# UltrasonicSensorArray.net
KiCad netlist of a schematic drawn in EAGLE
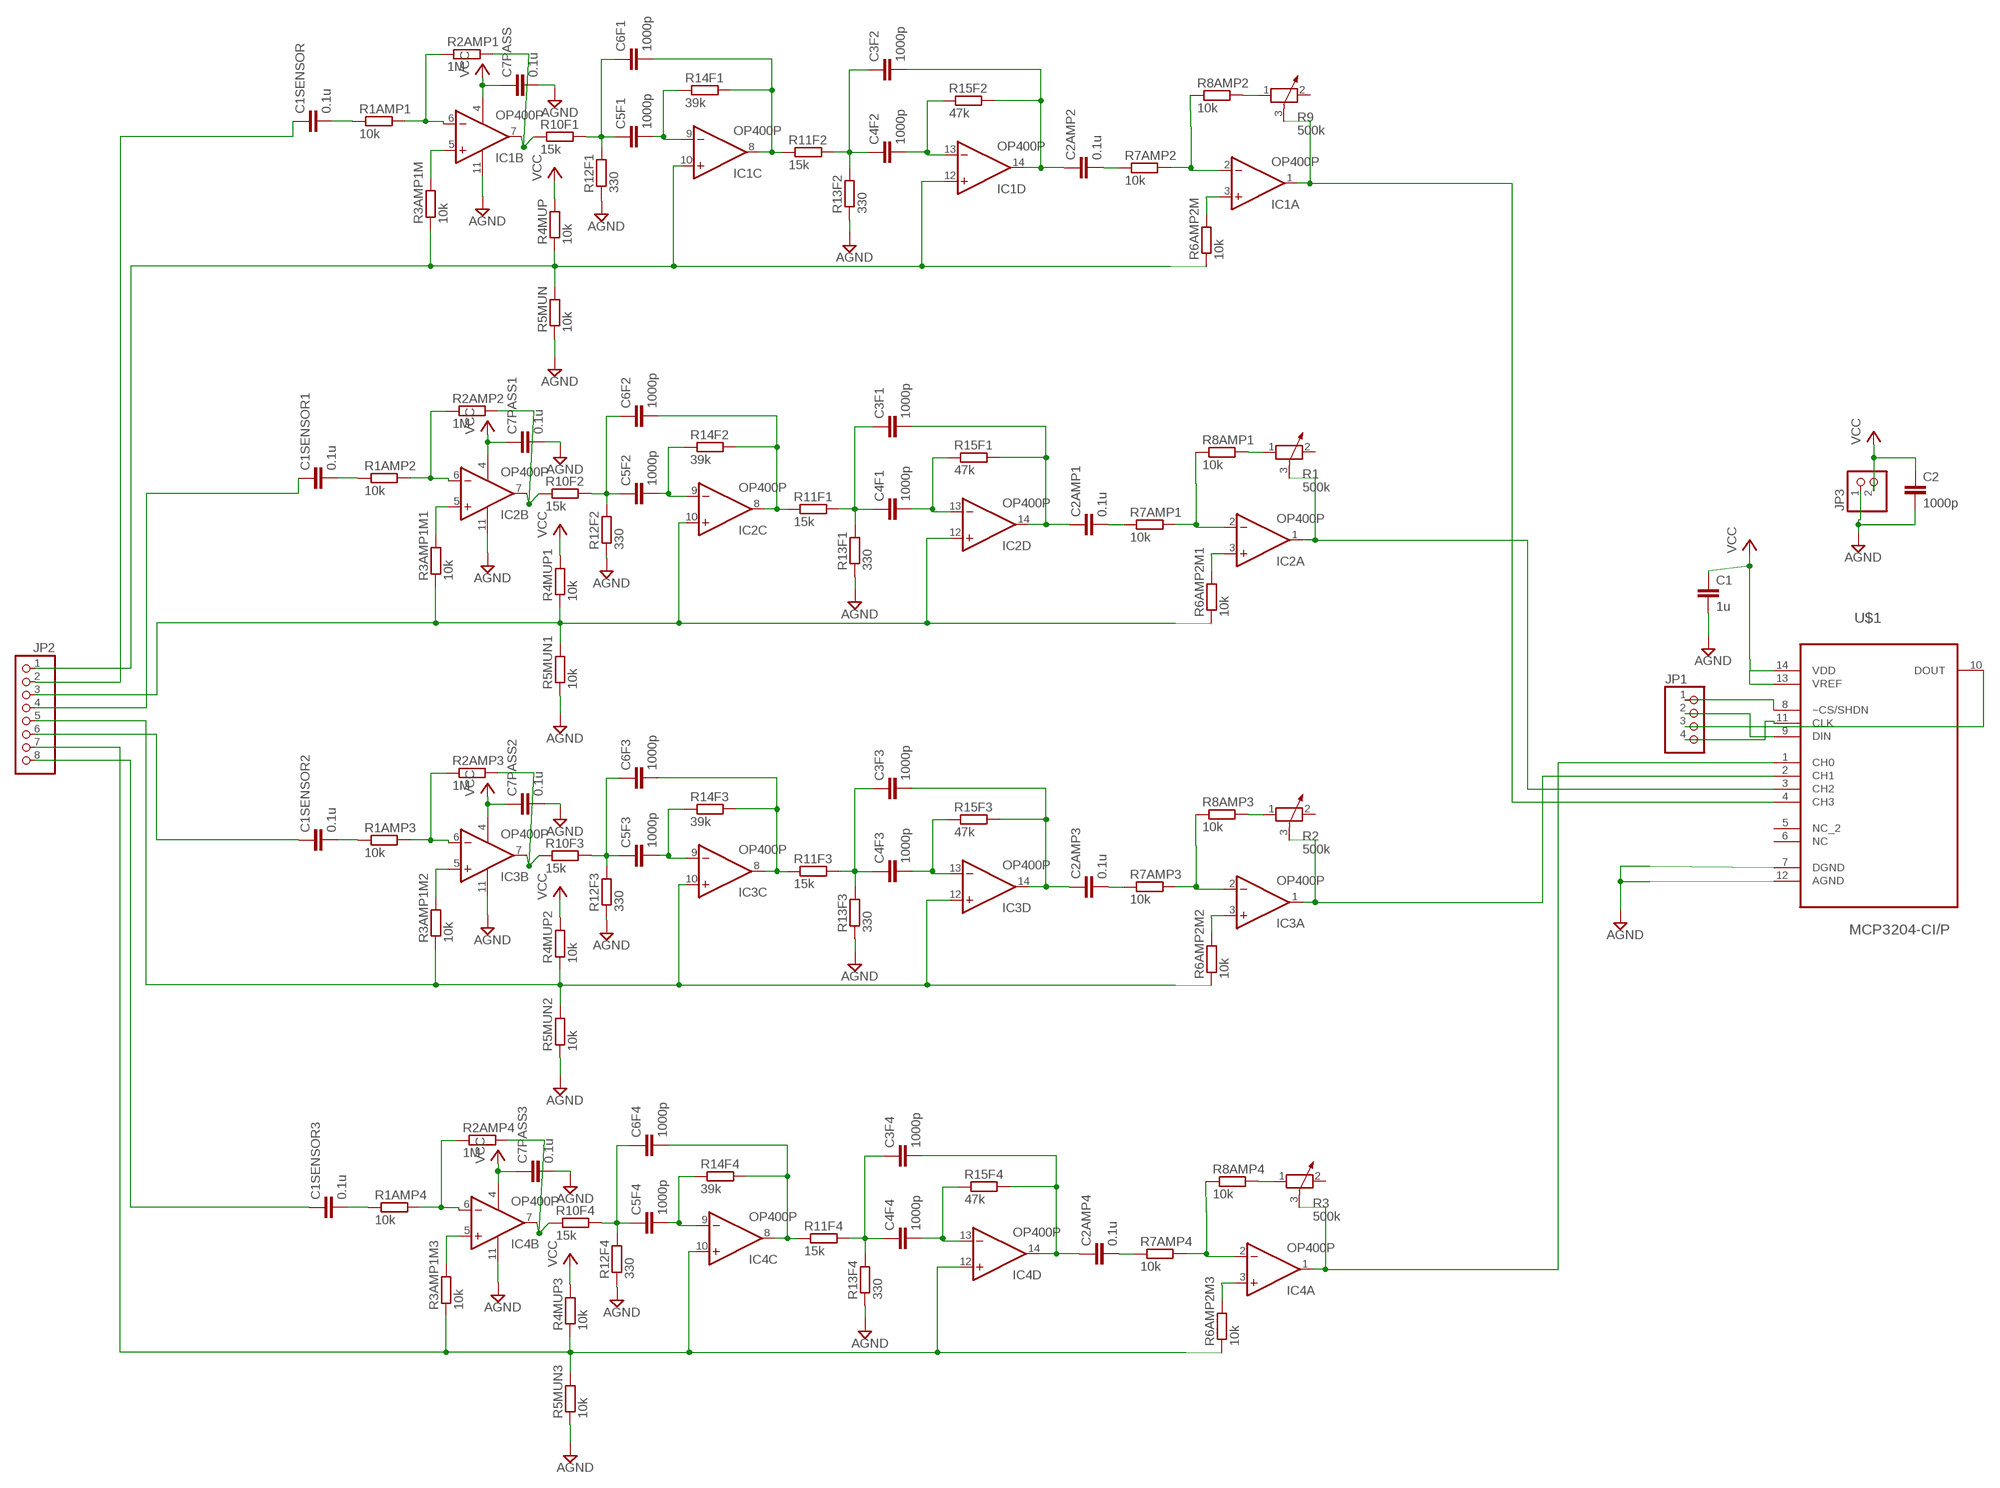
[diagram p0: schematic, sheet 1]

(export (version "E")
  (design (tool "Eeschema 10.0.6"))
  (components
    (comp (ref "C1")
      (value "1u")
      (footprint "eagle-import:C0603K")
      (libsource (lib "eagle-import") (part "C-EUC0603K"))
    )
    (comp (ref "C1SENSOR")
      (value "0.1u")
      (footprint "eagle-import:C0603K")
      (libsource (lib "eagle-import") (part "C-EUC0603K"))
    )
    (comp (ref "C1SENSOR1")
      (value "0.1u")
      (footprint "eagle-import:C0603K")
      (libsource (lib "eagle-import") (part "C-EUC0603K"))
    )
    (comp (ref "C1SENSOR2")
      (value "0.1u")
      (footprint "eagle-import:C0603K")
      (libsource (lib "eagle-import") (part "C-EUC0603K"))
    )
    (comp (ref "C1SENSOR3")
      (value "0.1u")
      (footprint "eagle-import:C0603K")
      (libsource (lib "eagle-import") (part "C-EUC0603K"))
    )
    (comp (ref "C2")
      (value "1000p")
      (footprint "eagle-import:C0603K")
      (libsource (lib "eagle-import") (part "C-EUC0603K"))
    )
    (comp (ref "C2AMP1")
      (value "0.1u")
      (footprint "eagle-import:C0603K")
      (libsource (lib "eagle-import") (part "C-EUC0603K"))
    )
    (comp (ref "C2AMP2")
      (value "0.1u")
      (footprint "eagle-import:C0603K")
      (libsource (lib "eagle-import") (part "C-EUC0603K"))
    )
    (comp (ref "C2AMP3")
      (value "0.1u")
      (footprint "eagle-import:C0603K")
      (libsource (lib "eagle-import") (part "C-EUC0603K"))
    )
    (comp (ref "C2AMP4")
      (value "0.1u")
      (footprint "eagle-import:C0603K")
      (libsource (lib "eagle-import") (part "C-EUC0603K"))
    )
    (comp (ref "C3F1")
      (value "1000p")
      (footprint "eagle-import:C0603K")
      (libsource (lib "eagle-import") (part "C-EUC0603K"))
    )
    (comp (ref "C3F2")
      (value "1000p")
      (footprint "eagle-import:C0603K")
      (libsource (lib "eagle-import") (part "C-EUC0603K"))
    )
    (comp (ref "C3F3")
      (value "1000p")
      (footprint "eagle-import:C0603K")
      (libsource (lib "eagle-import") (part "C-EUC0603K"))
    )
    (comp (ref "C3F4")
      (value "1000p")
      (footprint "eagle-import:C0603K")
      (libsource (lib "eagle-import") (part "C-EUC0603K"))
    )
    (comp (ref "C4F1")
      (value "1000p")
      (footprint "eagle-import:C0603K")
      (libsource (lib "eagle-import") (part "C-EUC0603K"))
    )
    (comp (ref "C4F2")
      (value "1000p")
      (footprint "eagle-import:C0603K")
      (libsource (lib "eagle-import") (part "C-EUC0603K"))
    )
    (comp (ref "C4F3")
      (value "1000p")
      (footprint "eagle-import:C0603K")
      (libsource (lib "eagle-import") (part "C-EUC0603K"))
    )
    (comp (ref "C4F4")
      (value "1000p")
      (footprint "eagle-import:C0603K")
      (libsource (lib "eagle-import") (part "C-EUC0603K"))
    )
    (comp (ref "C5F1")
      (value "1000p")
      (footprint "eagle-import:C0603K")
      (libsource (lib "eagle-import") (part "C-EUC0603K"))
    )
    (comp (ref "C5F2")
      (value "1000p")
      (footprint "eagle-import:C0603K")
      (libsource (lib "eagle-import") (part "C-EUC0603K"))
    )
    (comp (ref "C5F3")
      (value "1000p")
      (footprint "eagle-import:C0603K")
      (libsource (lib "eagle-import") (part "C-EUC0603K"))
    )
    (comp (ref "C5F4")
      (value "1000p")
      (footprint "eagle-import:C0603K")
      (libsource (lib "eagle-import") (part "C-EUC0603K"))
    )
    (comp (ref "C6F1")
      (value "1000p")
      (footprint "eagle-import:C0603K")
      (libsource (lib "eagle-import") (part "C-EUC0603K"))
    )
    (comp (ref "C6F2")
      (value "1000p")
      (footprint "eagle-import:C0603K")
      (libsource (lib "eagle-import") (part "C-EUC0603K"))
    )
    (comp (ref "C6F3")
      (value "1000p")
      (footprint "eagle-import:C0603K")
      (libsource (lib "eagle-import") (part "C-EUC0603K"))
    )
    (comp (ref "C6F4")
      (value "1000p")
      (footprint "eagle-import:C0603K")
      (libsource (lib "eagle-import") (part "C-EUC0603K"))
    )
    (comp (ref "C7PASS")
      (value "0.1u")
      (footprint "eagle-import:C0603K")
      (libsource (lib "eagle-import") (part "C-EUC0603K"))
    )
    (comp (ref "C7PASS1")
      (value "0.1u")
      (footprint "eagle-import:C0603K")
      (libsource (lib "eagle-import") (part "C-EUC0603K"))
    )
    (comp (ref "C7PASS2")
      (value "0.1u")
      (footprint "eagle-import:C0603K")
      (libsource (lib "eagle-import") (part "C-EUC0603K"))
    )
    (comp (ref "C7PASS3")
      (value "0.1u")
      (footprint "eagle-import:C0603K")
      (libsource (lib "eagle-import") (part "C-EUC0603K"))
    )
    (comp (ref "IC1")
      (value "OP400P")
      (footprint "eagle-import:DIL14")
      (libsource (lib "eagle-import") (part "OP400P"))
    )
    (comp (ref "IC2")
      (value "OP400P")
      (footprint "eagle-import:DIL14")
      (libsource (lib "eagle-import") (part "OP400P"))
    )
    (comp (ref "IC3")
      (value "OP400P")
      (footprint "eagle-import:DIL14")
      (libsource (lib "eagle-import") (part "OP400P"))
    )
    (comp (ref "IC4")
      (value "OP400P")
      (footprint "eagle-import:DIL14")
      (libsource (lib "eagle-import") (part "OP400P"))
    )
    (comp (ref "JP1")
      (value "PINHD-1X4")
      (footprint "eagle-import:1X04")
      (libsource (lib "eagle-import") (part "PINHD-1X4"))
    )
    (comp (ref "JP2")
      (value "PINHD-1X8")
      (footprint "eagle-import:1X08")
      (libsource (lib "eagle-import") (part "PINHD-1X8"))
    )
    (comp (ref "JP3")
      (value "PINHD-1X2")
      (footprint "eagle-import:1X02")
      (libsource (lib "eagle-import") (part "PINHD-1X2"))
    )
    (comp (ref "R1")
      (value "500k")
      (footprint "eagle-import:PT-10")
      (libsource (lib "eagle-import") (part "POTENTIOMETER_PT-10"))
    )
    (comp (ref "R1AMP1")
      (value "10k")
      (footprint "eagle-import:R0603")
      (libsource (lib "eagle-import") (part "R-EU_R0603"))
    )
    (comp (ref "R1AMP2")
      (value "10k")
      (footprint "eagle-import:R0603")
      (libsource (lib "eagle-import") (part "R-EU_R0603"))
    )
    (comp (ref "R1AMP3")
      (value "10k")
      (footprint "eagle-import:R0603")
      (libsource (lib "eagle-import") (part "R-EU_R0603"))
    )
    (comp (ref "R1AMP4")
      (value "10k")
      (footprint "eagle-import:R0603")
      (libsource (lib "eagle-import") (part "R-EU_R0603"))
    )
    (comp (ref "R2")
      (value "500k")
      (footprint "eagle-import:PT-10")
      (libsource (lib "eagle-import") (part "POTENTIOMETER_PT-10"))
    )
    (comp (ref "R2AMP1")
      (value "1M")
      (footprint "eagle-import:R0603")
      (libsource (lib "eagle-import") (part "R-EU_R0603"))
    )
    (comp (ref "R2AMP2")
      (value "1M")
      (footprint "eagle-import:R0603")
      (libsource (lib "eagle-import") (part "R-EU_R0603"))
    )
    (comp (ref "R2AMP3")
      (value "1M")
      (footprint "eagle-import:R0603")
      (libsource (lib "eagle-import") (part "R-EU_R0603"))
    )
    (comp (ref "R2AMP4")
      (value "1M")
      (footprint "eagle-import:R0603")
      (libsource (lib "eagle-import") (part "R-EU_R0603"))
    )
    (comp (ref "R3")
      (value "500k")
      (footprint "eagle-import:PT-10")
      (libsource (lib "eagle-import") (part "POTENTIOMETER_PT-10"))
    )
    (comp (ref "R3AMP1M")
      (value "10k")
      (footprint "eagle-import:R0603")
      (libsource (lib "eagle-import") (part "R-EU_R0603"))
    )
    (comp (ref "R3AMP1M1")
      (value "10k")
      (footprint "eagle-import:R0603")
      (libsource (lib "eagle-import") (part "R-EU_R0603"))
    )
    (comp (ref "R3AMP1M2")
      (value "10k")
      (footprint "eagle-import:R0603")
      (libsource (lib "eagle-import") (part "R-EU_R0603"))
    )
    (comp (ref "R3AMP1M3")
      (value "10k")
      (footprint "eagle-import:R0603")
      (libsource (lib "eagle-import") (part "R-EU_R0603"))
    )
    (comp (ref "R4MUP")
      (value "10k")
      (footprint "eagle-import:R0603")
      (libsource (lib "eagle-import") (part "R-EU_R0603"))
    )
    (comp (ref "R4MUP1")
      (value "10k")
      (footprint "eagle-import:R0603")
      (libsource (lib "eagle-import") (part "R-EU_R0603"))
    )
    (comp (ref "R4MUP2")
      (value "10k")
      (footprint "eagle-import:R0603")
      (libsource (lib "eagle-import") (part "R-EU_R0603"))
    )
    (comp (ref "R4MUP3")
      (value "10k")
      (footprint "eagle-import:R0603")
      (libsource (lib "eagle-import") (part "R-EU_R0603"))
    )
    (comp (ref "R5MUN")
      (value "10k")
      (footprint "eagle-import:R0603")
      (libsource (lib "eagle-import") (part "R-EU_R0603"))
    )
    (comp (ref "R5MUN1")
      (value "10k")
      (footprint "eagle-import:R0603")
      (libsource (lib "eagle-import") (part "R-EU_R0603"))
    )
    (comp (ref "R5MUN2")
      (value "10k")
      (footprint "eagle-import:R0603")
      (libsource (lib "eagle-import") (part "R-EU_R0603"))
    )
    (comp (ref "R5MUN3")
      (value "10k")
      (footprint "eagle-import:R0603")
      (libsource (lib "eagle-import") (part "R-EU_R0603"))
    )
    (comp (ref "R6AMP2M")
      (value "10k")
      (footprint "eagle-import:R0603")
      (libsource (lib "eagle-import") (part "R-EU_R0603"))
    )
    (comp (ref "R6AMP2M1")
      (value "10k")
      (footprint "eagle-import:R0603")
      (libsource (lib "eagle-import") (part "R-EU_R0603"))
    )
    (comp (ref "R6AMP2M2")
      (value "10k")
      (footprint "eagle-import:R0603")
      (libsource (lib "eagle-import") (part "R-EU_R0603"))
    )
    (comp (ref "R6AMP2M3")
      (value "10k")
      (footprint "eagle-import:R0603")
      (libsource (lib "eagle-import") (part "R-EU_R0603"))
    )
    (comp (ref "R7AMP1")
      (value "10k")
      (footprint "eagle-import:R0603")
      (libsource (lib "eagle-import") (part "R-EU_R0603"))
    )
    (comp (ref "R7AMP2")
      (value "10k")
      (footprint "eagle-import:R0603")
      (libsource (lib "eagle-import") (part "R-EU_R0603"))
    )
    (comp (ref "R7AMP3")
      (value "10k")
      (footprint "eagle-import:R0603")
      (libsource (lib "eagle-import") (part "R-EU_R0603"))
    )
    (comp (ref "R7AMP4")
      (value "10k")
      (footprint "eagle-import:R0603")
      (libsource (lib "eagle-import") (part "R-EU_R0603"))
    )
    (comp (ref "R8AMP1")
      (value "10k")
      (footprint "eagle-import:R0603")
      (libsource (lib "eagle-import") (part "R-EU_R0603"))
    )
    (comp (ref "R8AMP2")
      (value "10k")
      (footprint "eagle-import:R0603")
      (libsource (lib "eagle-import") (part "R-EU_R0603"))
    )
    (comp (ref "R8AMP3")
      (value "10k")
      (footprint "eagle-import:R0603")
      (libsource (lib "eagle-import") (part "R-EU_R0603"))
    )
    (comp (ref "R8AMP4")
      (value "10k")
      (footprint "eagle-import:R0603")
      (libsource (lib "eagle-import") (part "R-EU_R0603"))
    )
    (comp (ref "R9")
      (value "500k")
      (footprint "eagle-import:PT-10")
      (libsource (lib "eagle-import") (part "POTENTIOMETER_PT-10"))
    )
    (comp (ref "R10F1")
      (value "15k")
      (footprint "eagle-import:R0603")
      (libsource (lib "eagle-import") (part "R-EU_R0603"))
    )
    (comp (ref "R10F2")
      (value "15k")
      (footprint "eagle-import:R0603")
      (libsource (lib "eagle-import") (part "R-EU_R0603"))
    )
    (comp (ref "R10F3")
      (value "15k")
      (footprint "eagle-import:R0603")
      (libsource (lib "eagle-import") (part "R-EU_R0603"))
    )
    (comp (ref "R10F4")
      (value "15k")
      (footprint "eagle-import:R0603")
      (libsource (lib "eagle-import") (part "R-EU_R0603"))
    )
    (comp (ref "R11F1")
      (value "15k")
      (footprint "eagle-import:R0603")
      (libsource (lib "eagle-import") (part "R-EU_R0603"))
    )
    (comp (ref "R11F2")
      (value "15k")
      (footprint "eagle-import:R0603")
      (libsource (lib "eagle-import") (part "R-EU_R0603"))
    )
    (comp (ref "R11F3")
      (value "15k")
      (footprint "eagle-import:R0603")
      (libsource (lib "eagle-import") (part "R-EU_R0603"))
    )
    (comp (ref "R11F4")
      (value "15k")
      (footprint "eagle-import:R0603")
      (libsource (lib "eagle-import") (part "R-EU_R0603"))
    )
    (comp (ref "R12F1")
      (value "330")
      (footprint "eagle-import:R0603")
      (libsource (lib "eagle-import") (part "R-EU_R0603"))
    )
    (comp (ref "R12F2")
      (value "330")
      (footprint "eagle-import:R0603")
      (libsource (lib "eagle-import") (part "R-EU_R0603"))
    )
    (comp (ref "R12F3")
      (value "330")
      (footprint "eagle-import:R0603")
      (libsource (lib "eagle-import") (part "R-EU_R0603"))
    )
    (comp (ref "R12F4")
      (value "330")
      (footprint "eagle-import:R0603")
      (libsource (lib "eagle-import") (part "R-EU_R0603"))
    )
    (comp (ref "R13F1")
      (value "330")
      (footprint "eagle-import:R0603")
      (libsource (lib "eagle-import") (part "R-EU_R0603"))
    )
    (comp (ref "R13F2")
      (value "330")
      (footprint "eagle-import:R0603")
      (libsource (lib "eagle-import") (part "R-EU_R0603"))
    )
    (comp (ref "R13F3")
      (value "330")
      (footprint "eagle-import:R0603")
      (libsource (lib "eagle-import") (part "R-EU_R0603"))
    )
    (comp (ref "R13F4")
      (value "330")
      (footprint "eagle-import:R0603")
      (libsource (lib "eagle-import") (part "R-EU_R0603"))
    )
    (comp (ref "R14F1")
      (value "39k")
      (footprint "eagle-import:0207_7")
      (libsource (lib "eagle-import") (part "R-EU_0207/7"))
    )
    (comp (ref "R14F2")
      (value "39k")
      (footprint "eagle-import:0207_7")
      (libsource (lib "eagle-import") (part "R-EU_0207/7"))
    )
    (comp (ref "R14F3")
      (value "39k")
      (footprint "eagle-import:0207_7")
      (libsource (lib "eagle-import") (part "R-EU_0207/7"))
    )
    (comp (ref "R14F4")
      (value "39k")
      (footprint "eagle-import:0207_7")
      (libsource (lib "eagle-import") (part "R-EU_0207/7"))
    )
    (comp (ref "R15F1")
      (value "47k")
      (footprint "eagle-import:0207_7")
      (libsource (lib "eagle-import") (part "R-EU_0207/7"))
    )
    (comp (ref "R15F2")
      (value "47k")
      (footprint "eagle-import:0207_7")
      (libsource (lib "eagle-import") (part "R-EU_0207/7"))
    )
    (comp (ref "R15F3")
      (value "47k")
      (footprint "eagle-import:0207_7")
      (libsource (lib "eagle-import") (part "R-EU_0207/7"))
    )
    (comp (ref "R15F4")
      (value "47k")
      (footprint "eagle-import:0207_7")
      (libsource (lib "eagle-import") (part "R-EU_0207/7"))
    )
    (comp (ref "U$1")
      (value "MCP3204-CI/P")
      (footprint "eagle-import:DIP254P762X432-14")
      (fields (field (name "MF") "Microchip"))
      (libsource (lib "eagle-import") (part "MCP3204-CI/P"))
    )
  )
  (nets
    (net (code "1") (name "AGND") (class "Default")
      (node (ref "C1") (pin "2") (pinfunction "2_2") (pintype "passive"))
      (node (ref "C2") (pin "2") (pinfunction "2_2") (pintype "passive"))
      (node (ref "C7PASS") (pin "2") (pinfunction "2_2") (pintype "passive"))
      (node (ref "C7PASS1") (pin "2") (pinfunction "2_2") (pintype "passive"))
      (node (ref "C7PASS2") (pin "2") (pinfunction "2_2") (pintype "passive"))
      (node (ref "C7PASS3") (pin "2") (pinfunction "2_2") (pintype "passive"))
      (node (ref "IC1") (pin "11") (pinfunction "V-_11") (pintype "power_in"))
      (node (ref "IC2") (pin "11") (pinfunction "V-_11") (pintype "power_in"))
      (node (ref "IC3") (pin "11") (pinfunction "V-_11") (pintype "power_in"))
      (node (ref "IC4") (pin "11") (pinfunction "V-_11") (pintype "power_in"))
      (node (ref "JP3") (pin "1") (pinfunction "1_1") (pintype "passive"))
      (node (ref "R12F1") (pin "1") (pinfunction "1_1") (pintype "passive"))
      (node (ref "R12F2") (pin "1") (pinfunction "1_1") (pintype "passive"))
      (node (ref "R12F3") (pin "1") (pinfunction "1_1") (pintype "passive"))
      (node (ref "R12F4") (pin "1") (pinfunction "1_1") (pintype "passive"))
      (node (ref "R13F1") (pin "1") (pinfunction "1_1") (pintype "passive"))
      (node (ref "R13F2") (pin "1") (pinfunction "1_1") (pintype "passive"))
      (node (ref "R13F3") (pin "1") (pinfunction "1_1") (pintype "passive"))
      (node (ref "R13F4") (pin "1") (pinfunction "1_1") (pintype "passive"))
      (node (ref "R5MUN") (pin "1") (pinfunction "1_1") (pintype "passive"))
      (node (ref "R5MUN1") (pin "1") (pinfunction "1_1") (pintype "passive"))
      (node (ref "R5MUN2") (pin "1") (pinfunction "1_1") (pintype "passive"))
      (node (ref "R5MUN3") (pin "1") (pinfunction "1_1") (pintype "passive"))
      (node (ref "U$1") (pin "12") (pinfunction "AGND_12") (pintype "passive"))
      (node (ref "U$1") (pin "7") (pinfunction "DGND_7") (pintype "passive"))
    )
    (net (code "2") (name "Net-(C1SENSOR-Pad1)") (class "Default")
      (node (ref "C1SENSOR") (pin "1") (pinfunction "1_1") (pintype "passive"))
      (node (ref "JP2") (pin "2") (pinfunction "2_2") (pintype "passive"))
    )
    (net (code "3") (name "Net-(C1SENSOR-Pad2)") (class "Default")
      (node (ref "C1SENSOR") (pin "2") (pinfunction "2_2") (pintype "passive"))
      (node (ref "R1AMP1") (pin "1") (pinfunction "1_1") (pintype "passive"))
    )
    (net (code "4") (name "Net-(C1SENSOR1-Pad1)") (class "Default")
      (node (ref "C1SENSOR1") (pin "1") (pinfunction "1_1") (pintype "passive"))
      (node (ref "JP2") (pin "4") (pinfunction "4_4") (pintype "passive"))
    )
    (net (code "5") (name "Net-(C1SENSOR1-Pad2)") (class "Default")
      (node (ref "C1SENSOR1") (pin "2") (pinfunction "2_2") (pintype "passive"))
      (node (ref "R1AMP2") (pin "1") (pinfunction "1_1") (pintype "passive"))
    )
    (net (code "6") (name "Net-(C1SENSOR2-Pad1)") (class "Default")
      (node (ref "C1SENSOR2") (pin "1") (pinfunction "1_1") (pintype "passive"))
      (node (ref "JP2") (pin "6") (pinfunction "6_6") (pintype "passive"))
    )
    (net (code "7") (name "Net-(C1SENSOR2-Pad2)") (class "Default")
      (node (ref "C1SENSOR2") (pin "2") (pinfunction "2_2") (pintype "passive"))
      (node (ref "R1AMP3") (pin "1") (pinfunction "1_1") (pintype "passive"))
    )
    (net (code "8") (name "Net-(C1SENSOR3-Pad1)") (class "Default")
      (node (ref "C1SENSOR3") (pin "1") (pinfunction "1_1") (pintype "passive"))
      (node (ref "JP2") (pin "8") (pinfunction "8_8") (pintype "passive"))
    )
    (net (code "9") (name "Net-(C1SENSOR3-Pad2)") (class "Default")
      (node (ref "C1SENSOR3") (pin "2") (pinfunction "2_2") (pintype "passive"))
      (node (ref "R1AMP4") (pin "1") (pinfunction "1_1") (pintype "passive"))
    )
    (net (code "10") (name "Net-(C2AMP1-Pad2)") (class "Default")
      (node (ref "C2AMP1") (pin "2") (pinfunction "2_2") (pintype "passive"))
      (node (ref "R7AMP1") (pin "1") (pinfunction "1_1") (pintype "passive"))
    )
    (net (code "11") (name "Net-(C2AMP2-Pad2)") (class "Default")
      (node (ref "C2AMP2") (pin "2") (pinfunction "2_2") (pintype "passive"))
      (node (ref "R7AMP2") (pin "1") (pinfunction "1_1") (pintype "passive"))
    )
    (net (code "12") (name "Net-(C2AMP3-Pad2)") (class "Default")
      (node (ref "C2AMP3") (pin "2") (pinfunction "2_2") (pintype "passive"))
      (node (ref "R7AMP3") (pin "1") (pinfunction "1_1") (pintype "passive"))
    )
    (net (code "13") (name "Net-(C2AMP4-Pad2)") (class "Default")
      (node (ref "C2AMP4") (pin "2") (pinfunction "2_2") (pintype "passive"))
      (node (ref "R7AMP4") (pin "1") (pinfunction "1_1") (pintype "passive"))
    )
    (net (code "14") (name "Net-(C3F1-Pad1)") (class "Default")
      (node (ref "C3F1") (pin "1") (pinfunction "1_1") (pintype "passive"))
      (node (ref "C4F1") (pin "1") (pinfunction "1_1") (pintype "passive"))
      (node (ref "R11F1") (pin "2") (pinfunction "2_2") (pintype "passive"))
      (node (ref "R13F1") (pin "2") (pinfunction "2_2") (pintype "passive"))
    )
    (net (code "15") (name "Net-(C3F2-Pad1)") (class "Default")
      (node (ref "C3F2") (pin "1") (pinfunction "1_1") (pintype "passive"))
      (node (ref "C4F2") (pin "1") (pinfunction "1_1") (pintype "passive"))
      (node (ref "R11F2") (pin "2") (pinfunction "2_2") (pintype "passive"))
      (node (ref "R13F2") (pin "2") (pinfunction "2_2") (pintype "passive"))
    )
    (net (code "16") (name "Net-(C3F3-Pad1)") (class "Default")
      (node (ref "C3F3") (pin "1") (pinfunction "1_1") (pintype "passive"))
      (node (ref "C4F3") (pin "1") (pinfunction "1_1") (pintype "passive"))
      (node (ref "R11F3") (pin "2") (pinfunction "2_2") (pintype "passive"))
      (node (ref "R13F3") (pin "2") (pinfunction "2_2") (pintype "passive"))
    )
    (net (code "17") (name "Net-(C3F4-Pad1)") (class "Default")
      (node (ref "C3F4") (pin "1") (pinfunction "1_1") (pintype "passive"))
      (node (ref "C4F4") (pin "1") (pinfunction "1_1") (pintype "passive"))
      (node (ref "R11F4") (pin "2") (pinfunction "2_2") (pintype "passive"))
      (node (ref "R13F4") (pin "2") (pinfunction "2_2") (pintype "passive"))
    )
    (net (code "18") (name "Net-(C5F1-Pad1)") (class "Default")
      (node (ref "C5F1") (pin "1") (pinfunction "1_1") (pintype "passive"))
      (node (ref "C6F1") (pin "1") (pinfunction "1_1") (pintype "passive"))
      (node (ref "R10F1") (pin "2") (pinfunction "2_2") (pintype "passive"))
      (node (ref "R12F1") (pin "2") (pinfunction "2_2") (pintype "passive"))
    )
    (net (code "19") (name "Net-(C5F2-Pad1)") (class "Default")
      (node (ref "C5F2") (pin "1") (pinfunction "1_1") (pintype "passive"))
      (node (ref "C6F2") (pin "1") (pinfunction "1_1") (pintype "passive"))
      (node (ref "R10F2") (pin "2") (pinfunction "2_2") (pintype "passive"))
      (node (ref "R12F2") (pin "2") (pinfunction "2_2") (pintype "passive"))
    )
    (net (code "20") (name "Net-(C5F3-Pad1)") (class "Default")
      (node (ref "C5F3") (pin "1") (pinfunction "1_1") (pintype "passive"))
      (node (ref "C6F3") (pin "1") (pinfunction "1_1") (pintype "passive"))
      (node (ref "R10F3") (pin "2") (pinfunction "2_2") (pintype "passive"))
      (node (ref "R12F3") (pin "2") (pinfunction "2_2") (pintype "passive"))
    )
    (net (code "21") (name "Net-(C5F4-Pad1)") (class "Default")
      (node (ref "C5F4") (pin "1") (pinfunction "1_1") (pintype "passive"))
      (node (ref "C6F4") (pin "1") (pinfunction "1_1") (pintype "passive"))
      (node (ref "R10F4") (pin "2") (pinfunction "2_2") (pintype "passive"))
      (node (ref "R12F4") (pin "2") (pinfunction "2_2") (pintype "passive"))
    )
    (net (code "22") (name "Net-(IC1A-+IN)") (class "Default")
      (node (ref "IC1") (pin "3") (pinfunction "+IN_3") (pintype "input"))
      (node (ref "R6AMP2M") (pin "2") (pinfunction "2_2") (pintype "passive"))
    )
    (net (code "23") (name "Net-(IC1A--IN)") (class "Default")
      (node (ref "IC1") (pin "2") (pinfunction "-IN_2") (pintype "input"))
      (node (ref "R7AMP2") (pin "2") (pinfunction "2_2") (pintype "passive"))
      (node (ref "R8AMP2") (pin "1") (pinfunction "1_1") (pintype "passive"))
    )
    (net (code "24") (name "Net-(IC1A-OUT)") (class "Default")
      (node (ref "IC1") (pin "1") (pinfunction "OUT_1") (pintype "output"))
      (node (ref "R9") (pin "3") (pinfunction "3_3") (pintype "passive"))
      (node (ref "U$1") (pin "4") (pinfunction "CH3_4") (pintype "input"))
    )
    (net (code "25") (name "Net-(IC1B-+IN)") (class "Default")
      (node (ref "IC1") (pin "5") (pinfunction "+IN_5") (pintype "input"))
      (node (ref "R3AMP1M") (pin "2") (pinfunction "2_2") (pintype "passive"))
    )
    (net (code "26") (name "Net-(IC1B--IN)") (class "Default")
      (node (ref "IC1") (pin "6") (pinfunction "-IN_6") (pintype "input"))
      (node (ref "R1AMP1") (pin "2") (pinfunction "2_2") (pintype "passive"))
      (node (ref "R2AMP1") (pin "1") (pinfunction "1_1") (pintype "passive"))
    )
    (net (code "27") (name "Net-(IC1B-OUT)") (class "Default")
      (node (ref "IC1") (pin "7") (pinfunction "OUT_7") (pintype "output"))
      (node (ref "R10F1") (pin "1") (pinfunction "1_1") (pintype "passive"))
      (node (ref "R2AMP1") (pin "2") (pinfunction "2_2") (pintype "passive"))
    )
    (net (code "28") (name "Net-(IC1C-+IN)") (class "Default")
      (node (ref "IC1") (pin "10") (pinfunction "+IN_10") (pintype "input"))
      (node (ref "IC1") (pin "12") (pinfunction "+IN_12") (pintype "input"))
      (node (ref "JP2") (pin "1") (pinfunction "1_1") (pintype "passive"))
      (node (ref "R3AMP1M") (pin "1") (pinfunction "1_1") (pintype "passive"))
      (node (ref "R4MUP") (pin "1") (pinfunction "1_1") (pintype "passive"))
      (node (ref "R5MUN") (pin "2") (pinfunction "2_2") (pintype "passive"))
      (node (ref "R6AMP2M") (pin "1") (pinfunction "1_1") (pintype "passive"))
    )
    (net (code "29") (name "Net-(IC1C--IN)") (class "Default")
      (node (ref "C5F1") (pin "2") (pinfunction "2_2") (pintype "passive"))
      (node (ref "IC1") (pin "9") (pinfunction "-IN_9") (pintype "input"))
      (node (ref "R14F1") (pin "1") (pinfunction "1_1") (pintype "passive"))
    )
    (net (code "30") (name "Net-(IC1C-OUT)") (class "Default")
      (node (ref "C6F1") (pin "2") (pinfunction "2_2") (pintype "passive"))
      (node (ref "IC1") (pin "8") (pinfunction "OUT_8") (pintype "output"))
      (node (ref "R11F2") (pin "1") (pinfunction "1_1") (pintype "passive"))
      (node (ref "R14F1") (pin "2") (pinfunction "2_2") (pintype "passive"))
    )
    (net (code "31") (name "Net-(IC1D--IN)") (class "Default")
      (node (ref "C4F2") (pin "2") (pinfunction "2_2") (pintype "passive"))
      (node (ref "IC1") (pin "13") (pinfunction "-IN_13") (pintype "input"))
      (node (ref "R15F2") (pin "1") (pinfunction "1_1") (pintype "passive"))
    )
    (net (code "32") (name "Net-(IC1D-OUT)") (class "Default")
      (node (ref "C2AMP2") (pin "1") (pinfunction "1_1") (pintype "passive"))
      (node (ref "C3F2") (pin "2") (pinfunction "2_2") (pintype "passive"))
      (node (ref "IC1") (pin "14") (pinfunction "OUT_14") (pintype "output"))
      (node (ref "R15F2") (pin "2") (pinfunction "2_2") (pintype "passive"))
    )
    (net (code "33") (name "Net-(IC2A-+IN)") (class "Default")
      (node (ref "IC2") (pin "3") (pinfunction "+IN_3") (pintype "input"))
      (node (ref "R6AMP2M1") (pin "2") (pinfunction "2_2") (pintype "passive"))
    )
    (net (code "34") (name "Net-(IC2A--IN)") (class "Default")
      (node (ref "IC2") (pin "2") (pinfunction "-IN_2") (pintype "input"))
      (node (ref "R7AMP1") (pin "2") (pinfunction "2_2") (pintype "passive"))
      (node (ref "R8AMP1") (pin "1") (pinfunction "1_1") (pintype "passive"))
    )
    (net (code "35") (name "Net-(IC2A-OUT)") (class "Default")
      (node (ref "IC2") (pin "1") (pinfunction "OUT_1") (pintype "output"))
      (node (ref "R1") (pin "3") (pinfunction "3_3") (pintype "passive"))
      (node (ref "U$1") (pin "3") (pinfunction "CH2_3") (pintype "input"))
    )
    (net (code "36") (name "Net-(IC2B-+IN)") (class "Default")
      (node (ref "IC2") (pin "5") (pinfunction "+IN_5") (pintype "input"))
      (node (ref "R3AMP1M1") (pin "2") (pinfunction "2_2") (pintype "passive"))
    )
    (net (code "37") (name "Net-(IC2B--IN)") (class "Default")
      (node (ref "IC2") (pin "6") (pinfunction "-IN_6") (pintype "input"))
      (node (ref "R1AMP2") (pin "2") (pinfunction "2_2") (pintype "passive"))
      (node (ref "R2AMP2") (pin "1") (pinfunction "1_1") (pintype "passive"))
    )
    (net (code "38") (name "Net-(IC2B-OUT)") (class "Default")
      (node (ref "IC2") (pin "7") (pinfunction "OUT_7") (pintype "output"))
      (node (ref "R10F2") (pin "1") (pinfunction "1_1") (pintype "passive"))
      (node (ref "R2AMP2") (pin "2") (pinfunction "2_2") (pintype "passive"))
    )
    (net (code "39") (name "Net-(IC2C-+IN)") (class "Default")
      (node (ref "IC2") (pin "10") (pinfunction "+IN_10") (pintype "input"))
      (node (ref "IC2") (pin "12") (pinfunction "+IN_12") (pintype "input"))
      (node (ref "JP2") (pin "3") (pinfunction "3_3") (pintype "passive"))
      (node (ref "R3AMP1M1") (pin "1") (pinfunction "1_1") (pintype "passive"))
      (node (ref "R4MUP1") (pin "1") (pinfunction "1_1") (pintype "passive"))
      (node (ref "R5MUN1") (pin "2") (pinfunction "2_2") (pintype "passive"))
      (node (ref "R6AMP2M1") (pin "1") (pinfunction "1_1") (pintype "passive"))
    )
    (net (code "40") (name "Net-(IC2C--IN)") (class "Default")
      (node (ref "C5F2") (pin "2") (pinfunction "2_2") (pintype "passive"))
      (node (ref "IC2") (pin "9") (pinfunction "-IN_9") (pintype "input"))
      (node (ref "R14F2") (pin "1") (pinfunction "1_1") (pintype "passive"))
    )
    (net (code "41") (name "Net-(IC2C-OUT)") (class "Default")
      (node (ref "C6F2") (pin "2") (pinfunction "2_2") (pintype "passive"))
      (node (ref "IC2") (pin "8") (pinfunction "OUT_8") (pintype "output"))
      (node (ref "R11F1") (pin "1") (pinfunction "1_1") (pintype "passive"))
      (node (ref "R14F2") (pin "2") (pinfunction "2_2") (pintype "passive"))
    )
    (net (code "42") (name "Net-(IC2D--IN)") (class "Default")
      (node (ref "C4F1") (pin "2") (pinfunction "2_2") (pintype "passive"))
      (node (ref "IC2") (pin "13") (pinfunction "-IN_13") (pintype "input"))
      (node (ref "R15F1") (pin "1") (pinfunction "1_1") (pintype "passive"))
    )
    (net (code "43") (name "Net-(IC2D-OUT)") (class "Default")
      (node (ref "C2AMP1") (pin "1") (pinfunction "1_1") (pintype "passive"))
      (node (ref "C3F1") (pin "2") (pinfunction "2_2") (pintype "passive"))
      (node (ref "IC2") (pin "14") (pinfunction "OUT_14") (pintype "output"))
      (node (ref "R15F1") (pin "2") (pinfunction "2_2") (pintype "passive"))
    )
    (net (code "44") (name "Net-(IC3A-+IN)") (class "Default")
      (node (ref "IC3") (pin "3") (pinfunction "+IN_3") (pintype "input"))
      (node (ref "R6AMP2M2") (pin "2") (pinfunction "2_2") (pintype "passive"))
    )
    (net (code "45") (name "Net-(IC3A--IN)") (class "Default")
      (node (ref "IC3") (pin "2") (pinfunction "-IN_2") (pintype "input"))
      (node (ref "R7AMP3") (pin "2") (pinfunction "2_2") (pintype "passive"))
      (node (ref "R8AMP3") (pin "1") (pinfunction "1_1") (pintype "passive"))
    )
    (net (code "46") (name "Net-(IC3A-OUT)") (class "Default")
      (node (ref "IC3") (pin "1") (pinfunction "OUT_1") (pintype "output"))
      (node (ref "R2") (pin "3") (pinfunction "3_3") (pintype "passive"))
      (node (ref "U$1") (pin "2") (pinfunction "CH1_2") (pintype "input"))
    )
    (net (code "47") (name "Net-(IC3B-+IN)") (class "Default")
      (node (ref "IC3") (pin "5") (pinfunction "+IN_5") (pintype "input"))
      (node (ref "R3AMP1M2") (pin "2") (pinfunction "2_2") (pintype "passive"))
    )
    (net (code "48") (name "Net-(IC3B--IN)") (class "Default")
      (node (ref "IC3") (pin "6") (pinfunction "-IN_6") (pintype "input"))
      (node (ref "R1AMP3") (pin "2") (pinfunction "2_2") (pintype "passive"))
      (node (ref "R2AMP3") (pin "1") (pinfunction "1_1") (pintype "passive"))
    )
    (net (code "49") (name "Net-(IC3B-OUT)") (class "Default")
      (node (ref "IC3") (pin "7") (pinfunction "OUT_7") (pintype "output"))
      (node (ref "R10F3") (pin "1") (pinfunction "1_1") (pintype "passive"))
      (node (ref "R2AMP3") (pin "2") (pinfunction "2_2") (pintype "passive"))
    )
    (net (code "50") (name "Net-(IC3C-+IN)") (class "Default")
      (node (ref "IC3") (pin "10") (pinfunction "+IN_10") (pintype "input"))
      (node (ref "IC3") (pin "12") (pinfunction "+IN_12") (pintype "input"))
      (node (ref "JP2") (pin "5") (pinfunction "5_5") (pintype "passive"))
      (node (ref "R3AMP1M2") (pin "1") (pinfunction "1_1") (pintype "passive"))
      (node (ref "R4MUP2") (pin "1") (pinfunction "1_1") (pintype "passive"))
      (node (ref "R5MUN2") (pin "2") (pinfunction "2_2") (pintype "passive"))
      (node (ref "R6AMP2M2") (pin "1") (pinfunction "1_1") (pintype "passive"))
    )
    (net (code "51") (name "Net-(IC3C--IN)") (class "Default")
      (node (ref "C5F3") (pin "2") (pinfunction "2_2") (pintype "passive"))
      (node (ref "IC3") (pin "9") (pinfunction "-IN_9") (pintype "input"))
      (node (ref "R14F3") (pin "1") (pinfunction "1_1") (pintype "passive"))
    )
    (net (code "52") (name "Net-(IC3C-OUT)") (class "Default")
      (node (ref "C6F3") (pin "2") (pinfunction "2_2") (pintype "passive"))
      (node (ref "IC3") (pin "8") (pinfunction "OUT_8") (pintype "output"))
      (node (ref "R11F3") (pin "1") (pinfunction "1_1") (pintype "passive"))
      (node (ref "R14F3") (pin "2") (pinfunction "2_2") (pintype "passive"))
    )
    (net (code "53") (name "Net-(IC3D--IN)") (class "Default")
      (node (ref "C4F3") (pin "2") (pinfunction "2_2") (pintype "passive"))
      (node (ref "IC3") (pin "13") (pinfunction "-IN_13") (pintype "input"))
      (node (ref "R15F3") (pin "1") (pinfunction "1_1") (pintype "passive"))
    )
    (net (code "54") (name "Net-(IC3D-OUT)") (class "Default")
      (node (ref "C2AMP3") (pin "1") (pinfunction "1_1") (pintype "passive"))
      (node (ref "C3F3") (pin "2") (pinfunction "2_2") (pintype "passive"))
      (node (ref "IC3") (pin "14") (pinfunction "OUT_14") (pintype "output"))
      (node (ref "R15F3") (pin "2") (pinfunction "2_2") (pintype "passive"))
    )
    (net (code "55") (name "Net-(IC4A-+IN)") (class "Default")
      (node (ref "IC4") (pin "3") (pinfunction "+IN_3") (pintype "input"))
      (node (ref "R6AMP2M3") (pin "2") (pinfunction "2_2") (pintype "passive"))
    )
    (net (code "56") (name "Net-(IC4A--IN)") (class "Default")
      (node (ref "IC4") (pin "2") (pinfunction "-IN_2") (pintype "input"))
      (node (ref "R7AMP4") (pin "2") (pinfunction "2_2") (pintype "passive"))
      (node (ref "R8AMP4") (pin "1") (pinfunction "1_1") (pintype "passive"))
    )
    (net (code "57") (name "Net-(IC4A-OUT)") (class "Default")
      (node (ref "IC4") (pin "1") (pinfunction "OUT_1") (pintype "output"))
      (node (ref "R3") (pin "3") (pinfunction "3_3") (pintype "passive"))
      (node (ref "U$1") (pin "1") (pinfunction "CH0_1") (pintype "input"))
    )
    (net (code "58") (name "Net-(IC4B-+IN)") (class "Default")
      (node (ref "IC4") (pin "5") (pinfunction "+IN_5") (pintype "input"))
      (node (ref "R3AMP1M3") (pin "2") (pinfunction "2_2") (pintype "passive"))
    )
    (net (code "59") (name "Net-(IC4B--IN)") (class "Default")
      (node (ref "IC4") (pin "6") (pinfunction "-IN_6") (pintype "input"))
      (node (ref "R1AMP4") (pin "2") (pinfunction "2_2") (pintype "passive"))
      (node (ref "R2AMP4") (pin "1") (pinfunction "1_1") (pintype "passive"))
    )
    (net (code "60") (name "Net-(IC4B-OUT)") (class "Default")
      (node (ref "IC4") (pin "7") (pinfunction "OUT_7") (pintype "output"))
      (node (ref "R10F4") (pin "1") (pinfunction "1_1") (pintype "passive"))
      (node (ref "R2AMP4") (pin "2") (pinfunction "2_2") (pintype "passive"))
    )
    (net (code "61") (name "Net-(IC4C-+IN)") (class "Default")
      (node (ref "IC4") (pin "10") (pinfunction "+IN_10") (pintype "input"))
      (node (ref "IC4") (pin "12") (pinfunction "+IN_12") (pintype "input"))
      (node (ref "JP2") (pin "7") (pinfunction "7_7") (pintype "passive"))
      (node (ref "R3AMP1M3") (pin "1") (pinfunction "1_1") (pintype "passive"))
      (node (ref "R4MUP3") (pin "1") (pinfunction "1_1") (pintype "passive"))
      (node (ref "R5MUN3") (pin "2") (pinfunction "2_2") (pintype "passive"))
      (node (ref "R6AMP2M3") (pin "1") (pinfunction "1_1") (pintype "passive"))
    )
    (net (code "62") (name "Net-(IC4C--IN)") (class "Default")
      (node (ref "C5F4") (pin "2") (pinfunction "2_2") (pintype "passive"))
      (node (ref "IC4") (pin "9") (pinfunction "-IN_9") (pintype "input"))
      (node (ref "R14F4") (pin "1") (pinfunction "1_1") (pintype "passive"))
    )
    (net (code "63") (name "Net-(IC4C-OUT)") (class "Default")
      (node (ref "C6F4") (pin "2") (pinfunction "2_2") (pintype "passive"))
      (node (ref "IC4") (pin "8") (pinfunction "OUT_8") (pintype "output"))
      (node (ref "R11F4") (pin "1") (pinfunction "1_1") (pintype "passive"))
      (node (ref "R14F4") (pin "2") (pinfunction "2_2") (pintype "passive"))
    )
    (net (code "64") (name "Net-(IC4D--IN)") (class "Default")
      (node (ref "C4F4") (pin "2") (pinfunction "2_2") (pintype "passive"))
      (node (ref "IC4") (pin "13") (pinfunction "-IN_13") (pintype "input"))
      (node (ref "R15F4") (pin "1") (pinfunction "1_1") (pintype "passive"))
    )
    (net (code "65") (name "Net-(IC4D-OUT)") (class "Default")
      (node (ref "C2AMP4") (pin "1") (pinfunction "1_1") (pintype "passive"))
      (node (ref "C3F4") (pin "2") (pinfunction "2_2") (pintype "passive"))
      (node (ref "IC4") (pin "14") (pinfunction "OUT_14") (pintype "output"))
      (node (ref "R15F4") (pin "2") (pinfunction "2_2") (pintype "passive"))
    )
    (net (code "66") (name "Net-(R1-Pad1)") (class "Default")
      (node (ref "R1") (pin "1") (pinfunction "1_1") (pintype "passive"))
      (node (ref "R8AMP1") (pin "2") (pinfunction "2_2") (pintype "passive"))
    )
    (net (code "67") (name "Net-(R2-Pad1)") (class "Default")
      (node (ref "R2") (pin "1") (pinfunction "1_1") (pintype "passive"))
      (node (ref "R8AMP3") (pin "2") (pinfunction "2_2") (pintype "passive"))
    )
    (net (code "68") (name "Net-(R3-Pad1)") (class "Default")
      (node (ref "R3") (pin "1") (pinfunction "1_1") (pintype "passive"))
      (node (ref "R8AMP4") (pin "2") (pinfunction "2_2") (pintype "passive"))
    )
    (net (code "69") (name "Net-(R8AMP2-Pad2)") (class "Default")
      (node (ref "R8AMP2") (pin "2") (pinfunction "2_2") (pintype "passive"))
      (node (ref "R9") (pin "1") (pinfunction "1_1") (pintype "passive"))
    )
    (net (code "70") (name "Net-(U$1-CLK)") (class "Default")
      (node (ref "JP1") (pin "4") (pinfunction "4_4") (pintype "passive"))
      (node (ref "U$1") (pin "11") (pinfunction "CLK_11") (pintype "input"))
    )
    (net (code "71") (name "Net-(U$1-DIN)") (class "Default")
      (node (ref "JP1") (pin "2") (pinfunction "2_2") (pintype "passive"))
      (node (ref "U$1") (pin "9") (pinfunction "DIN_9") (pintype "input"))
    )
    (net (code "72") (name "Net-(U$1-DOUT)") (class "Default")
      (node (ref "JP1") (pin "3") (pinfunction "3_3") (pintype "passive"))
      (node (ref "U$1") (pin "10") (pinfunction "DOUT_10") (pintype "output"))
    )
    (net (code "73") (name "Net-(U$1-~{CS{slash}SHDN})") (class "Default")
      (node (ref "JP1") (pin "1") (pinfunction "1_1") (pintype "passive"))
      (node (ref "U$1") (pin "8") (pinfunction "~{CS/SHDN}_8") (pintype "input"))
    )
    (net (code "74") (name "VCC") (class "Default")
      (node (ref "C1") (pin "1") (pinfunction "1_1") (pintype "passive"))
      (node (ref "C2") (pin "1") (pinfunction "1_1") (pintype "passive"))
      (node (ref "C7PASS") (pin "1") (pinfunction "1_1") (pintype "passive"))
      (node (ref "C7PASS1") (pin "1") (pinfunction "1_1") (pintype "passive"))
      (node (ref "C7PASS2") (pin "1") (pinfunction "1_1") (pintype "passive"))
      (node (ref "C7PASS3") (pin "1") (pinfunction "1_1") (pintype "passive"))
      (node (ref "IC1") (pin "4") (pinfunction "V+_4") (pintype "power_in"))
      (node (ref "IC2") (pin "4") (pinfunction "V+_4") (pintype "power_in"))
      (node (ref "IC3") (pin "4") (pinfunction "V+_4") (pintype "power_in"))
      (node (ref "IC4") (pin "4") (pinfunction "V+_4") (pintype "power_in"))
      (node (ref "JP3") (pin "2") (pinfunction "2_2") (pintype "passive"))
      (node (ref "R4MUP") (pin "2") (pinfunction "2_2") (pintype "passive"))
      (node (ref "R4MUP1") (pin "2") (pinfunction "2_2") (pintype "passive"))
      (node (ref "R4MUP2") (pin "2") (pinfunction "2_2") (pintype "passive"))
      (node (ref "R4MUP3") (pin "2") (pinfunction "2_2") (pintype "passive"))
      (node (ref "U$1") (pin "13") (pinfunction "VREF_13") (pintype "power_in"))
      (node (ref "U$1") (pin "14") (pinfunction "VDD_14") (pintype "power_in"))
    )
    (net (code "75") (name "unconnected-(R1-Pad2)") (class "Default")
      (node (ref "R1") (pin "2") (pinfunction "2_2") (pintype "passive"))
    )
    (net (code "76") (name "unconnected-(R2-Pad2)") (class "Default")
      (node (ref "R2") (pin "2") (pinfunction "2_2") (pintype "passive"))
    )
    (net (code "77") (name "unconnected-(R3-Pad2)") (class "Default")
      (node (ref "R3") (pin "2") (pinfunction "2_2") (pintype "passive"))
    )
    (net (code "78") (name "unconnected-(R9-Pad2)") (class "Default")
      (node (ref "R9") (pin "2") (pinfunction "2_2") (pintype "passive"))
    )
    (net (code "79") (name "unconnected-(U$1-NC-Pad6)") (class "Default")
      (node (ref "U$1") (pin "6") (pinfunction "NC_6") (pintype "no_connect"))
    )
    (net (code "80") (name "unconnected-(U$1-NC_2-Pad5)") (class "Default")
      (node (ref "U$1") (pin "5") (pinfunction "NC_2_5") (pintype "no_connect"))
    )
  )
)
